# WM-main_board1finalRev5_1.net
KiCad netlist of a schematic drawn in EAGLE
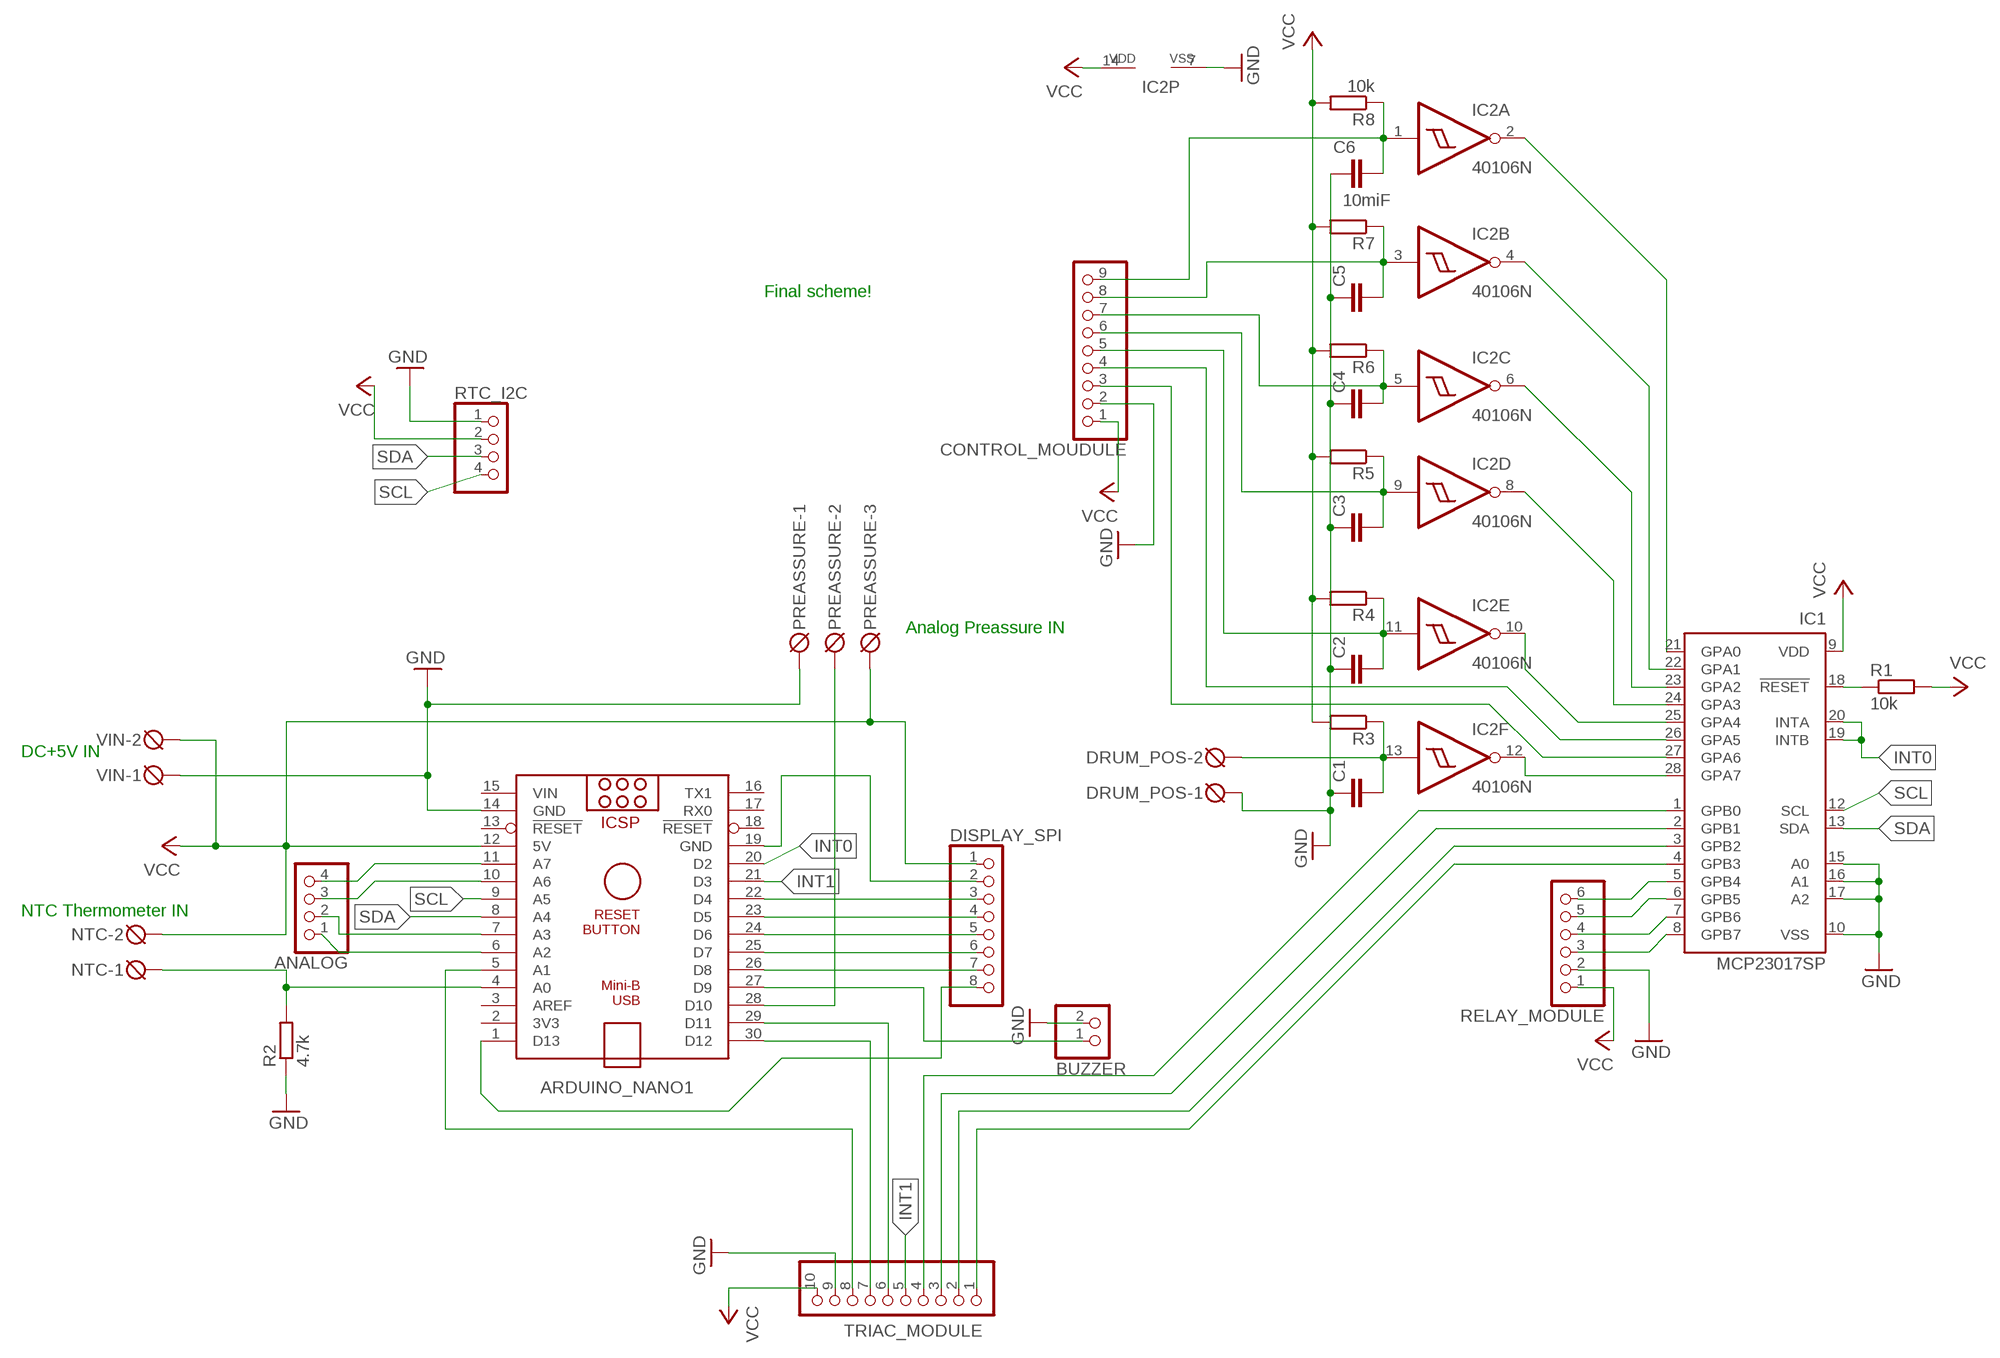
[diagram p0: schematic, sheet 1]

(export (version "E")
  (design (tool "Eeschema 10.0.6"))
  (components
    (comp (ref "ANALOG")
      (value "PINHD-1X4")
      (footprint "eagle-import:1X04")
      (libsource (lib "eagle-import") (part "PINHD-1X4"))
    )
    (comp (ref "ARDUINO_NANO1")
      (value "ARDUINO_NANO")
      (footprint "eagle-import:ARDUINO_NANO")
      (libsource (lib "eagle-import") (part "ARDUINO_NANO"))
    )
    (comp (ref "BUZZER")
      (value "PINHD-1X2")
      (footprint "eagle-import:1X02")
      (libsource (lib "eagle-import") (part "PINHD-1X2"))
    )
    (comp (ref "C1")
      (value "CC1206")
      (footprint "eagle-import:C1206")
      (libsource (lib "eagle-import") (part "CC1206"))
    )
    (comp (ref "C2")
      (value "CC1206")
      (footprint "eagle-import:C1206")
      (libsource (lib "eagle-import") (part "CC1206"))
    )
    (comp (ref "C3")
      (value "CC1206")
      (footprint "eagle-import:C1206")
      (libsource (lib "eagle-import") (part "CC1206"))
    )
    (comp (ref "C4")
      (value "CC1206")
      (footprint "eagle-import:C1206")
      (libsource (lib "eagle-import") (part "CC1206"))
    )
    (comp (ref "C5")
      (value "CC1206")
      (footprint "eagle-import:C1206")
      (libsource (lib "eagle-import") (part "CC1206"))
    )
    (comp (ref "C6")
      (value "10miF")
      (footprint "eagle-import:C1206")
      (libsource (lib "eagle-import") (part "CC1206"))
    )
    (comp (ref "CONTROL_MOUDULE")
      (value "PINHD-1X9")
      (footprint "eagle-import:1X09-BIG")
      (libsource (lib "eagle-import") (part "PINHD-1X9"))
    )
    (comp (ref "DISPLAY_SPI")
      (value "PINHD-1X8BIG")
      (footprint "eagle-import:1X08-BIG")
      (libsource (lib "eagle-import") (part "PINHD-1X8BIG"))
    )
    (comp (ref "DRUM_POS")
      (value "DRUM")
      (footprint "eagle-import:DG306-5.0-02P")
      (libsource (lib "eagle-import") (part "DG3XX-02-5.0"))
    )
    (comp (ref "IC1")
      (value "MCP23017SP")
      (footprint "eagle-import:DIL28-3")
      (libsource (lib "eagle-import") (part "MCP23017SP"))
    )
    (comp (ref "IC2")
      (value "40106N")
      (footprint "eagle-import:DIL14")
      (libsource (lib "eagle-import") (part "40106N"))
    )
    (comp (ref "NTC")
      (value "TEMP")
      (footprint "eagle-import:DG306-5.0-02P")
      (libsource (lib "eagle-import") (part "DG3XX-02-5.0"))
    )
    (comp (ref "PREASSURE")
      (value "GND D10 +5V(out)")
      (footprint "eagle-import:DG306-5.0-03P")
      (libsource (lib "eagle-import") (part "DG3XX-03-5.0"))
    )
    (comp (ref "R1")
      (value "10k")
      (footprint "eagle-import:0204_7")
      (libsource (lib "eagle-import") (part "R-EU_0204/7"))
    )
    (comp (ref "R2")
      (value "4.7k")
      (footprint "eagle-import:0204_7")
      (libsource (lib "eagle-import") (part "R-EU_0204/7"))
    )
    (comp (ref "R3")
      (value "R-EU_M1206")
      (footprint "eagle-import:M1206")
      (libsource (lib "eagle-import") (part "R-EU_M1206"))
    )
    (comp (ref "R4")
      (value "R-EU_M1206")
      (footprint "eagle-import:M1206")
      (libsource (lib "eagle-import") (part "R-EU_M1206"))
    )
    (comp (ref "R5")
      (value "R-EU_M1206")
      (footprint "eagle-import:M1206")
      (libsource (lib "eagle-import") (part "R-EU_M1206"))
    )
    (comp (ref "R6")
      (value "R-EU_M1206")
      (footprint "eagle-import:M1206")
      (libsource (lib "eagle-import") (part "R-EU_M1206"))
    )
    (comp (ref "R7")
      (value "R-EU_M1206")
      (footprint "eagle-import:M1206")
      (libsource (lib "eagle-import") (part "R-EU_M1206"))
    )
    (comp (ref "R8")
      (value "10k")
      (footprint "eagle-import:M1206")
      (libsource (lib "eagle-import") (part "R-EU_M1206"))
    )
    (comp (ref "RELAY_MODULE")
      (value "PINHD-1X6B")
      (footprint "eagle-import:1X06-BIG")
      (libsource (lib "eagle-import") (part "PINHD-1X6B"))
    )
    (comp (ref "RTC_I2C")
      (value "PINHD-1X4")
      (footprint "eagle-import:1X04")
      (libsource (lib "eagle-import") (part "PINHD-1X4"))
    )
    (comp (ref "TRIAC_MODULE")
      (value "PINHD-1X10")
      (footprint "eagle-import:1X10-BIG")
      (libsource (lib "eagle-import") (part "PINHD-1X10"))
    )
    (comp (ref "VIN")
      (value "GND +5V(IN)")
      (footprint "eagle-import:DG306-5.0-02P")
      (libsource (lib "eagle-import") (part "DG3XX-02-5.0"))
    )
  )
  (nets
    (net (code "1") (name "/VIN") (class "Default")
      (node (ref "ARDUINO_NANO1") (pin "15") (pinfunction "VIN_15") (pintype "power_in"))
    )
    (net (code "2") (name "GND") (class "Default")
      (node (ref "ARDUINO_NANO1") (pin "14") (pinfunction "GND_14") (pintype "power_in"))
      (node (ref "BUZZER") (pin "2") (pinfunction "2_2") (pintype "passive"))
      (node (ref "C1") (pin "1") (pinfunction "1_1") (pintype "passive"))
      (node (ref "C2") (pin "1") (pinfunction "1_1") (pintype "passive"))
      (node (ref "C3") (pin "1") (pinfunction "1_1") (pintype "passive"))
      (node (ref "C4") (pin "1") (pinfunction "1_1") (pintype "passive"))
      (node (ref "C5") (pin "1") (pinfunction "1_1") (pintype "passive"))
      (node (ref "C6") (pin "1") (pinfunction "1_1") (pintype "passive"))
      (node (ref "CONTROL_MOUDULE") (pin "2") (pinfunction "2_2") (pintype "passive"))
      (node (ref "DRUM_POS") (pin "1") (pinfunction "KL_1") (pintype "passive"))
      (node (ref "IC1") (pin "10") (pinfunction "VSS_10") (pintype "power_in"))
      (node (ref "IC1") (pin "15") (pinfunction "A0_15") (pintype "input"))
      (node (ref "IC1") (pin "16") (pinfunction "A1_16") (pintype "input"))
      (node (ref "IC1") (pin "17") (pinfunction "A2_17") (pintype "input"))
      (node (ref "IC2") (pin "7") (pinfunction "VSS_7") (pintype "power_in"))
      (node (ref "PREASSURE") (pin "1") (pinfunction "KL_1") (pintype "passive"))
      (node (ref "R2") (pin "1") (pinfunction "1_1") (pintype "passive"))
      (node (ref "RELAY_MODULE") (pin "2") (pinfunction "2_2") (pintype "passive"))
      (node (ref "RTC_I2C") (pin "1") (pinfunction "1_1") (pintype "passive"))
      (node (ref "TRIAC_MODULE") (pin "9") (pinfunction "9_9") (pintype "passive"))
      (node (ref "VIN") (pin "1") (pinfunction "KL_1") (pintype "passive"))
    )
    (net (code "3") (name "INT0") (class "Default")
      (node (ref "ARDUINO_NANO1") (pin "20") (pinfunction "D2_20") (pintype "bidirectional"))
      (node (ref "IC1") (pin "19") (pinfunction "INTB_19") (pintype "output"))
      (node (ref "IC1") (pin "20") (pinfunction "INTA_20") (pintype "output"))
    )
    (net (code "4") (name "INT1") (class "Default")
      (node (ref "ARDUINO_NANO1") (pin "21") (pinfunction "D3_21") (pintype "bidirectional"))
      (node (ref "TRIAC_MODULE") (pin "5") (pinfunction "5_5") (pintype "passive"))
    )
    (net (code "5") (name "Net-(ARDUINO_NANO1-A0)") (class "Default")
      (node (ref "ARDUINO_NANO1") (pin "4") (pinfunction "A0_4") (pintype "bidirectional"))
      (node (ref "NTC") (pin "1") (pinfunction "KL_1") (pintype "passive"))
      (node (ref "R2") (pin "2") (pinfunction "2_2") (pintype "passive"))
    )
    (net (code "6") (name "Net-(ARDUINO_NANO1-A1)") (class "Default")
      (node (ref "ARDUINO_NANO1") (pin "5") (pinfunction "A1_5") (pintype "bidirectional"))
      (node (ref "TRIAC_MODULE") (pin "8") (pinfunction "8_8") (pintype "passive"))
    )
    (net (code "7") (name "Net-(ARDUINO_NANO1-A2)") (class "Default")
      (node (ref "ANALOG") (pin "1") (pinfunction "1_1") (pintype "passive"))
      (node (ref "ARDUINO_NANO1") (pin "6") (pinfunction "A2_6") (pintype "bidirectional"))
    )
    (net (code "8") (name "Net-(ARDUINO_NANO1-A3)") (class "Default")
      (node (ref "ANALOG") (pin "2") (pinfunction "2_2") (pintype "passive"))
      (node (ref "ARDUINO_NANO1") (pin "7") (pinfunction "A3_7") (pintype "bidirectional"))
    )
    (net (code "9") (name "Net-(ARDUINO_NANO1-A6)") (class "Default")
      (node (ref "ANALOG") (pin "3") (pinfunction "3_3") (pintype "passive"))
      (node (ref "ARDUINO_NANO1") (pin "10") (pinfunction "A6_10") (pintype "bidirectional"))
    )
    (net (code "10") (name "Net-(ARDUINO_NANO1-A7)") (class "Default")
      (node (ref "ANALOG") (pin "4") (pinfunction "4_4") (pintype "passive"))
      (node (ref "ARDUINO_NANO1") (pin "11") (pinfunction "A7_11") (pintype "bidirectional"))
    )
    (net (code "11") (name "Net-(ARDUINO_NANO1-D4)") (class "Default")
      (node (ref "ARDUINO_NANO1") (pin "22") (pinfunction "D4_22") (pintype "bidirectional"))
      (node (ref "DISPLAY_SPI") (pin "3") (pinfunction "3_3") (pintype "passive"))
    )
    (net (code "12") (name "Net-(ARDUINO_NANO1-D5)") (class "Default")
      (node (ref "ARDUINO_NANO1") (pin "23") (pinfunction "D5_23") (pintype "bidirectional"))
      (node (ref "DISPLAY_SPI") (pin "4") (pinfunction "4_4") (pintype "passive"))
    )
    (net (code "13") (name "Net-(ARDUINO_NANO1-D6)") (class "Default")
      (node (ref "ARDUINO_NANO1") (pin "24") (pinfunction "D6_24") (pintype "bidirectional"))
      (node (ref "DISPLAY_SPI") (pin "5") (pinfunction "5_5") (pintype "passive"))
    )
    (net (code "14") (name "Net-(ARDUINO_NANO1-D7)") (class "Default")
      (node (ref "ARDUINO_NANO1") (pin "25") (pinfunction "D7_25") (pintype "bidirectional"))
      (node (ref "DISPLAY_SPI") (pin "6") (pinfunction "6_6") (pintype "passive"))
    )
    (net (code "15") (name "Net-(ARDUINO_NANO1-D8)") (class "Default")
      (node (ref "ARDUINO_NANO1") (pin "26") (pinfunction "D8_26") (pintype "bidirectional"))
      (node (ref "DISPLAY_SPI") (pin "7") (pinfunction "7_7") (pintype "passive"))
    )
    (net (code "16") (name "Net-(ARDUINO_NANO1-D9)") (class "Default")
      (node (ref "ARDUINO_NANO1") (pin "27") (pinfunction "D9_27") (pintype "bidirectional"))
      (node (ref "BUZZER") (pin "1") (pinfunction "1_1") (pintype "passive"))
    )
    (net (code "17") (name "Net-(ARDUINO_NANO1-D10)") (class "Default")
      (node (ref "ARDUINO_NANO1") (pin "28") (pinfunction "D10_28") (pintype "bidirectional"))
      (node (ref "PREASSURE") (pin "2") (pinfunction "KL_2") (pintype "passive"))
    )
    (net (code "18") (name "Net-(ARDUINO_NANO1-D11)") (class "Default")
      (node (ref "ARDUINO_NANO1") (pin "29") (pinfunction "D11_29") (pintype "bidirectional"))
      (node (ref "TRIAC_MODULE") (pin "6") (pinfunction "6_6") (pintype "passive"))
    )
    (net (code "19") (name "Net-(ARDUINO_NANO1-D12)") (class "Default")
      (node (ref "ARDUINO_NANO1") (pin "30") (pinfunction "D12_30") (pintype "bidirectional"))
      (node (ref "TRIAC_MODULE") (pin "7") (pinfunction "7_7") (pintype "passive"))
    )
    (net (code "20") (name "Net-(ARDUINO_NANO1-D13)") (class "Default")
      (node (ref "ARDUINO_NANO1") (pin "1") (pinfunction "D13_1") (pintype "bidirectional"))
      (node (ref "DISPLAY_SPI") (pin "8") (pinfunction "8_8") (pintype "passive"))
    )
    (net (code "21") (name "Net-(ARDUINO_NANO1-GND-Pad19)") (class "Default")
      (node (ref "ARDUINO_NANO1") (pin "19") (pinfunction "GND_19") (pintype "power_in"))
      (node (ref "DISPLAY_SPI") (pin "2") (pinfunction "2_2") (pintype "passive"))
    )
    (net (code "22") (name "Net-(DRUM_POSB-KL)") (class "Default")
      (node (ref "C1") (pin "2") (pinfunction "2_2") (pintype "passive"))
      (node (ref "DRUM_POS") (pin "2") (pinfunction "KL_2") (pintype "passive"))
      (node (ref "IC2") (pin "13") (pinfunction "I_13") (pintype "input"))
      (node (ref "R3") (pin "1") (pinfunction "1_1") (pintype "passive"))
    )
    (net (code "23") (name "Net-(IC1-GPA0)") (class "Default")
      (node (ref "IC1") (pin "21") (pinfunction "GPA0_21") (pintype "bidirectional"))
      (node (ref "IC2") (pin "2") (pinfunction "O_2") (pintype "output"))
    )
    (net (code "24") (name "Net-(IC1-GPA1)") (class "Default")
      (node (ref "IC1") (pin "22") (pinfunction "GPA1_22") (pintype "bidirectional"))
      (node (ref "IC2") (pin "4") (pinfunction "O_4") (pintype "output"))
    )
    (net (code "25") (name "Net-(IC1-GPA2)") (class "Default")
      (node (ref "IC1") (pin "23") (pinfunction "GPA2_23") (pintype "bidirectional"))
      (node (ref "IC2") (pin "6") (pinfunction "O_6") (pintype "output"))
    )
    (net (code "26") (name "Net-(IC1-GPA3)") (class "Default")
      (node (ref "IC1") (pin "24") (pinfunction "GPA3_24") (pintype "bidirectional"))
      (node (ref "IC2") (pin "8") (pinfunction "O_8") (pintype "output"))
    )
    (net (code "27") (name "Net-(IC1-GPA4)") (class "Default")
      (node (ref "IC1") (pin "25") (pinfunction "GPA4_25") (pintype "bidirectional"))
      (node (ref "IC2") (pin "10") (pinfunction "O_10") (pintype "output"))
    )
    (net (code "28") (name "Net-(IC1-GPA5)") (class "Default")
      (node (ref "CONTROL_MOUDULE") (pin "4") (pinfunction "4_4") (pintype "passive"))
      (node (ref "IC1") (pin "26") (pinfunction "GPA5_26") (pintype "bidirectional"))
    )
    (net (code "29") (name "Net-(IC1-GPA6)") (class "Default")
      (node (ref "CONTROL_MOUDULE") (pin "3") (pinfunction "3_3") (pintype "passive"))
      (node (ref "IC1") (pin "27") (pinfunction "GPA6_27") (pintype "bidirectional"))
    )
    (net (code "30") (name "Net-(IC1-GPA7)") (class "Default")
      (node (ref "IC1") (pin "28") (pinfunction "GPA7_28") (pintype "bidirectional"))
      (node (ref "IC2") (pin "12") (pinfunction "O_12") (pintype "output"))
    )
    (net (code "31") (name "Net-(IC1-GPB0)") (class "Default")
      (node (ref "IC1") (pin "1") (pinfunction "GPB0_1") (pintype "bidirectional"))
      (node (ref "TRIAC_MODULE") (pin "4") (pinfunction "4_4") (pintype "passive"))
    )
    (net (code "32") (name "Net-(IC1-GPB1)") (class "Default")
      (node (ref "IC1") (pin "2") (pinfunction "GPB1_2") (pintype "bidirectional"))
      (node (ref "TRIAC_MODULE") (pin "3") (pinfunction "3_3") (pintype "passive"))
    )
    (net (code "33") (name "Net-(IC1-GPB2)") (class "Default")
      (node (ref "IC1") (pin "3") (pinfunction "GPB2_3") (pintype "bidirectional"))
      (node (ref "TRIAC_MODULE") (pin "2") (pinfunction "2_2") (pintype "passive"))
    )
    (net (code "34") (name "Net-(IC1-GPB3)") (class "Default")
      (node (ref "IC1") (pin "4") (pinfunction "GPB3_4") (pintype "bidirectional"))
      (node (ref "TRIAC_MODULE") (pin "1") (pinfunction "1_1") (pintype "passive"))
    )
    (net (code "35") (name "Net-(IC1-GPB4)") (class "Default")
      (node (ref "IC1") (pin "5") (pinfunction "GPB4_5") (pintype "bidirectional"))
      (node (ref "RELAY_MODULE") (pin "6") (pinfunction "6_6") (pintype "passive"))
    )
    (net (code "36") (name "Net-(IC1-GPB5)") (class "Default")
      (node (ref "IC1") (pin "6") (pinfunction "GPB5_6") (pintype "bidirectional"))
      (node (ref "RELAY_MODULE") (pin "5") (pinfunction "5_5") (pintype "passive"))
    )
    (net (code "37") (name "Net-(IC1-GPB6)") (class "Default")
      (node (ref "IC1") (pin "7") (pinfunction "GPB6_7") (pintype "bidirectional"))
      (node (ref "RELAY_MODULE") (pin "4") (pinfunction "4_4") (pintype "passive"))
    )
    (net (code "38") (name "Net-(IC1-GPB7)") (class "Default")
      (node (ref "IC1") (pin "8") (pinfunction "GPB7_8") (pintype "bidirectional"))
      (node (ref "RELAY_MODULE") (pin "3") (pinfunction "3_3") (pintype "passive"))
    )
    (net (code "39") (name "Net-(IC1-~{RESET})") (class "Default")
      (node (ref "IC1") (pin "18") (pinfunction "~{RESET}_18") (pintype "input"))
      (node (ref "R1") (pin "1") (pinfunction "1_1") (pintype "passive"))
    )
    (net (code "40") (name "Net-(IC2A-I)") (class "Default")
      (node (ref "C6") (pin "2") (pinfunction "2_2") (pintype "passive"))
      (node (ref "CONTROL_MOUDULE") (pin "9") (pinfunction "9_9") (pintype "passive"))
      (node (ref "IC2") (pin "1") (pinfunction "I_1") (pintype "input"))
      (node (ref "R8") (pin "1") (pinfunction "1_1") (pintype "passive"))
    )
    (net (code "41") (name "Net-(IC2B-I)") (class "Default")
      (node (ref "C5") (pin "2") (pinfunction "2_2") (pintype "passive"))
      (node (ref "CONTROL_MOUDULE") (pin "8") (pinfunction "8_8") (pintype "passive"))
      (node (ref "IC2") (pin "3") (pinfunction "I_3") (pintype "input"))
      (node (ref "R7") (pin "1") (pinfunction "1_1") (pintype "passive"))
    )
    (net (code "42") (name "Net-(IC2C-I)") (class "Default")
      (node (ref "C4") (pin "2") (pinfunction "2_2") (pintype "passive"))
      (node (ref "CONTROL_MOUDULE") (pin "7") (pinfunction "7_7") (pintype "passive"))
      (node (ref "IC2") (pin "5") (pinfunction "I_5") (pintype "input"))
      (node (ref "R6") (pin "1") (pinfunction "1_1") (pintype "passive"))
    )
    (net (code "43") (name "Net-(IC2D-I)") (class "Default")
      (node (ref "C3") (pin "2") (pinfunction "2_2") (pintype "passive"))
      (node (ref "CONTROL_MOUDULE") (pin "6") (pinfunction "6_6") (pintype "passive"))
      (node (ref "IC2") (pin "9") (pinfunction "I_9") (pintype "input"))
      (node (ref "R5") (pin "1") (pinfunction "1_1") (pintype "passive"))
    )
    (net (code "44") (name "Net-(IC2E-I)") (class "Default")
      (node (ref "C2") (pin "2") (pinfunction "2_2") (pintype "passive"))
      (node (ref "CONTROL_MOUDULE") (pin "5") (pinfunction "5_5") (pintype "passive"))
      (node (ref "IC2") (pin "11") (pinfunction "I_11") (pintype "input"))
      (node (ref "R4") (pin "1") (pinfunction "1_1") (pintype "passive"))
    )
    (net (code "45") (name "SCL") (class "Default")
      (node (ref "ARDUINO_NANO1") (pin "9") (pinfunction "A5_9") (pintype "bidirectional"))
      (node (ref "IC1") (pin "12") (pinfunction "SCL_12") (pintype "input"))
      (node (ref "RTC_I2C") (pin "4") (pinfunction "4_4") (pintype "passive"))
    )
    (net (code "46") (name "SDA") (class "Default")
      (node (ref "ARDUINO_NANO1") (pin "8") (pinfunction "A4_8") (pintype "bidirectional"))
      (node (ref "IC1") (pin "13") (pinfunction "SDA_13") (pintype "bidirectional"))
      (node (ref "RTC_I2C") (pin "3") (pinfunction "3_3") (pintype "passive"))
    )
    (net (code "47") (name "VCC") (class "Default")
      (node (ref "ARDUINO_NANO1") (pin "12") (pinfunction "5V_12") (pintype "power_in"))
      (node (ref "CONTROL_MOUDULE") (pin "1") (pinfunction "1_1") (pintype "passive"))
      (node (ref "DISPLAY_SPI") (pin "1") (pinfunction "1_1") (pintype "passive"))
      (node (ref "IC1") (pin "9") (pinfunction "VDD_9") (pintype "power_in"))
      (node (ref "IC2") (pin "14") (pinfunction "VDD_14") (pintype "power_in"))
      (node (ref "NTC") (pin "2") (pinfunction "KL_2") (pintype "passive"))
      (node (ref "PREASSURE") (pin "3") (pinfunction "KL_3") (pintype "passive"))
      (node (ref "R1") (pin "2") (pinfunction "2_2") (pintype "passive"))
      (node (ref "R3") (pin "2") (pinfunction "2_2") (pintype "passive"))
      (node (ref "R4") (pin "2") (pinfunction "2_2") (pintype "passive"))
      (node (ref "R5") (pin "2") (pinfunction "2_2") (pintype "passive"))
      (node (ref "R6") (pin "2") (pinfunction "2_2") (pintype "passive"))
      (node (ref "R7") (pin "2") (pinfunction "2_2") (pintype "passive"))
      (node (ref "R8") (pin "2") (pinfunction "2_2") (pintype "passive"))
      (node (ref "RELAY_MODULE") (pin "1") (pinfunction "1_1") (pintype "passive"))
      (node (ref "RTC_I2C") (pin "2") (pinfunction "2_2") (pintype "passive"))
      (node (ref "TRIAC_MODULE") (pin "10") (pinfunction "10_10") (pintype "passive"))
      (node (ref "VIN") (pin "2") (pinfunction "KL_2") (pintype "passive"))
    )
    (net (code "48") (name "unconnected-(ARDUINO_NANO1-3V3-Pad2)") (class "Default")
      (node (ref "ARDUINO_NANO1") (pin "2") (pinfunction "3V3_2") (pintype "output"))
    )
    (net (code "49") (name "unconnected-(ARDUINO_NANO1-AREF-Pad3)") (class "Default")
      (node (ref "ARDUINO_NANO1") (pin "3") (pinfunction "AREF_3") (pintype "input"))
    )
    (net (code "50") (name "unconnected-(ARDUINO_NANO1-RX0-Pad17)") (class "Default")
      (node (ref "ARDUINO_NANO1") (pin "17") (pinfunction "RX0_17") (pintype "bidirectional"))
    )
    (net (code "51") (name "unconnected-(ARDUINO_NANO1-TX1-Pad16)") (class "Default")
      (node (ref "ARDUINO_NANO1") (pin "16") (pinfunction "TX1_16") (pintype "bidirectional"))
    )
    (net (code "52") (name "unconnected-(ARDUINO_NANO1-~{RESET}-Pad13)") (class "Default")
      (node (ref "ARDUINO_NANO1") (pin "13") (pinfunction "~{RESET}_13") (pintype "input"))
    )
    (net (code "53") (name "unconnected-(ARDUINO_NANO1-~{RESET}-Pad18)") (class "Default")
      (node (ref "ARDUINO_NANO1") (pin "18") (pinfunction "~{RESET}_18") (pintype "input"))
    )
  )
)
